# sensor1.net
KiCad netlist of a schematic drawn in EAGLE
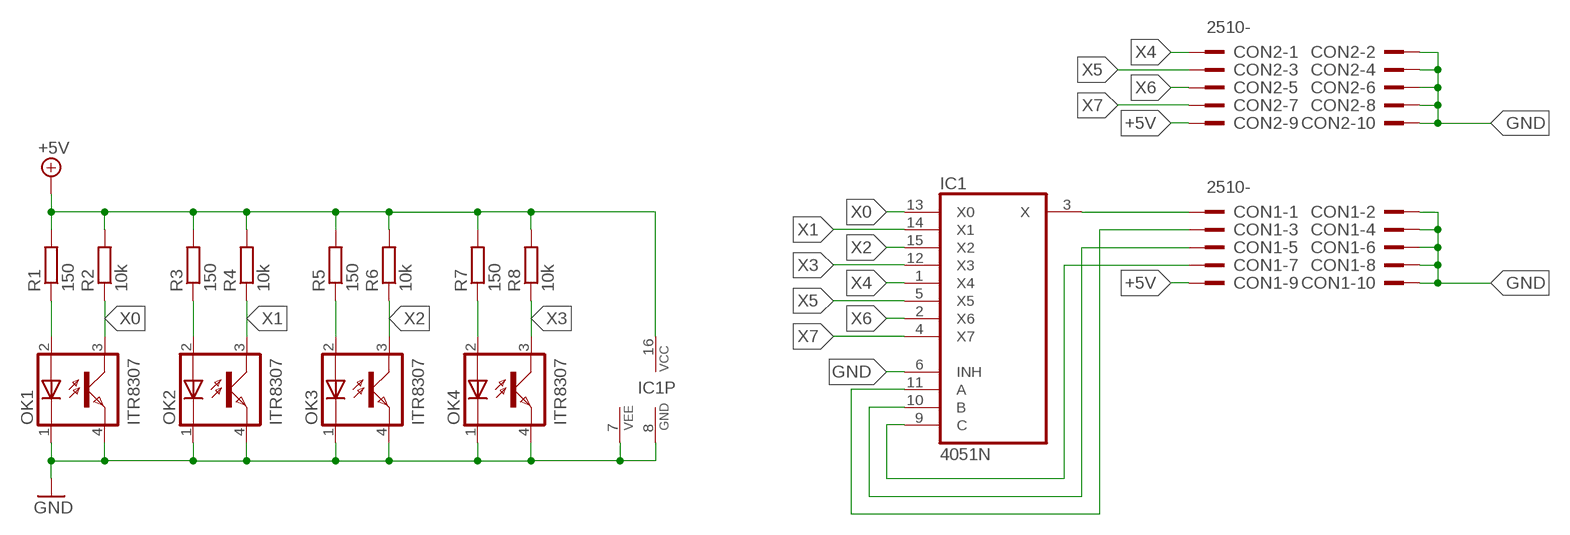
[diagram p0: schematic, sheet 1]

(export (version "E")
  (design (tool "Eeschema 10.0.6"))
  (components
    (comp (ref "CON1")
      (value "2510-")
      (footprint "eagle-import:PAK100_2500-10")
      (fields (field (name "MF") "3M") (field (name "MPN") "2510-6002UB"))
      (libsource (lib "eagle-import") (part "2510-"))
    )
    (comp (ref "CON2")
      (value "2510-")
      (footprint "eagle-import:PAK100_2500-10")
      (fields (field (name "MF") "3M") (field (name "MPN") "2510-6002UB"))
      (libsource (lib "eagle-import") (part "2510-"))
    )
    (comp (ref "IC1")
      (value "4051N")
      (footprint "eagle-import:DIL16")
      (libsource (lib "eagle-import") (part "4051N"))
    )
    (comp (ref "OK1")
      (value "ITR8307")
      (footprint "eagle-import:F43")
      (libsource (lib "eagle-import") (part "ITR8307"))
    )
    (comp (ref "OK2")
      (value "ITR8307")
      (footprint "eagle-import:F43")
      (libsource (lib "eagle-import") (part "ITR8307"))
    )
    (comp (ref "OK3")
      (value "ITR8307")
      (footprint "eagle-import:F43")
      (libsource (lib "eagle-import") (part "ITR8307"))
    )
    (comp (ref "OK4")
      (value "ITR8307")
      (footprint "eagle-import:F43")
      (libsource (lib "eagle-import") (part "ITR8307"))
    )
    (comp (ref "R1")
      (value "150")
      (footprint "eagle-import:0204_7")
      (libsource (lib "eagle-import") (part "R-EU_0204/7"))
    )
    (comp (ref "R2")
      (value "10k")
      (footprint "eagle-import:0204_7")
      (libsource (lib "eagle-import") (part "R-EU_0204/7"))
    )
    (comp (ref "R3")
      (value "150")
      (footprint "eagle-import:0204_7")
      (libsource (lib "eagle-import") (part "R-EU_0204/7"))
    )
    (comp (ref "R4")
      (value "10k")
      (footprint "eagle-import:0204_7")
      (libsource (lib "eagle-import") (part "R-EU_0204/7"))
    )
    (comp (ref "R5")
      (value "150")
      (footprint "eagle-import:0204_7")
      (libsource (lib "eagle-import") (part "R-EU_0204/7"))
    )
    (comp (ref "R6")
      (value "10k")
      (footprint "eagle-import:0204_7")
      (libsource (lib "eagle-import") (part "R-EU_0204/7"))
    )
    (comp (ref "R7")
      (value "150")
      (footprint "eagle-import:0204_7")
      (libsource (lib "eagle-import") (part "R-EU_0204/7"))
    )
    (comp (ref "R8")
      (value "10k")
      (footprint "eagle-import:0204_7")
      (libsource (lib "eagle-import") (part "R-EU_0204/7"))
    )
  )
  (nets
    (net (code "1") (name "+5V") (class "Default")
      (node (ref "CON1") (pin "9") (pinfunction "KL_9") (pintype "passive"))
      (node (ref "CON2") (pin "9") (pinfunction "KL_9") (pintype "passive"))
      (node (ref "IC1") (pin "16") (pinfunction "VCC_16") (pintype "power_in"))
      (node (ref "R1") (pin "2") (pinfunction "2_2") (pintype "passive"))
      (node (ref "R2") (pin "2") (pinfunction "2_2") (pintype "passive"))
      (node (ref "R3") (pin "2") (pinfunction "2_2") (pintype "passive"))
      (node (ref "R4") (pin "2") (pinfunction "2_2") (pintype "passive"))
      (node (ref "R5") (pin "2") (pinfunction "2_2") (pintype "passive"))
      (node (ref "R6") (pin "2") (pinfunction "2_2") (pintype "passive"))
      (node (ref "R7") (pin "2") (pinfunction "2_2") (pintype "passive"))
      (node (ref "R8") (pin "2") (pinfunction "2_2") (pintype "passive"))
    )
    (net (code "2") (name "GND") (class "Default")
      (node (ref "CON1") (pin "10") (pinfunction "KL_10") (pintype "passive"))
      (node (ref "CON1") (pin "2") (pinfunction "KL_2") (pintype "passive"))
      (node (ref "CON1") (pin "4") (pinfunction "KL_4") (pintype "passive"))
      (node (ref "CON1") (pin "6") (pinfunction "KL_6") (pintype "passive"))
      (node (ref "CON1") (pin "8") (pinfunction "KL_8") (pintype "passive"))
      (node (ref "CON2") (pin "10") (pinfunction "KL_10") (pintype "passive"))
      (node (ref "CON2") (pin "2") (pinfunction "KL_2") (pintype "passive"))
      (node (ref "CON2") (pin "4") (pinfunction "KL_4") (pintype "passive"))
      (node (ref "CON2") (pin "6") (pinfunction "KL_6") (pintype "passive"))
      (node (ref "CON2") (pin "8") (pinfunction "KL_8") (pintype "passive"))
      (node (ref "IC1") (pin "6") (pinfunction "INH_6") (pintype "input"))
      (node (ref "IC1") (pin "7") (pinfunction "VEE_7") (pintype "power_in"))
      (node (ref "IC1") (pin "8") (pinfunction "GND_8") (pintype "power_in"))
      (node (ref "OK1") (pin "1") (pinfunction "C_1") (pintype "passive"))
      (node (ref "OK1") (pin "4") (pinfunction "EMIT_4") (pintype "passive"))
      (node (ref "OK2") (pin "1") (pinfunction "C_1") (pintype "passive"))
      (node (ref "OK2") (pin "4") (pinfunction "EMIT_4") (pintype "passive"))
      (node (ref "OK3") (pin "1") (pinfunction "C_1") (pintype "passive"))
      (node (ref "OK3") (pin "4") (pinfunction "EMIT_4") (pintype "passive"))
      (node (ref "OK4") (pin "1") (pinfunction "C_1") (pintype "passive"))
      (node (ref "OK4") (pin "4") (pinfunction "EMIT_4") (pintype "passive"))
    )
    (net (code "3") (name "Net-(CON1A-KL)") (class "Default")
      (node (ref "CON1") (pin "1") (pinfunction "KL_1") (pintype "passive"))
      (node (ref "IC1") (pin "3") (pinfunction "X_3") (pintype "bidirectional"))
    )
    (net (code "4") (name "Net-(CON1D-KL)") (class "Default")
      (node (ref "CON1") (pin "3") (pinfunction "KL_3") (pintype "passive"))
      (node (ref "IC1") (pin "11") (pinfunction "A_11") (pintype "input"))
    )
    (net (code "5") (name "Net-(CON1F-KL)") (class "Default")
      (node (ref "CON1") (pin "5") (pinfunction "KL_5") (pintype "passive"))
      (node (ref "IC1") (pin "10") (pinfunction "B_10") (pintype "input"))
    )
    (net (code "6") (name "Net-(CON1H-KL)") (class "Default")
      (node (ref "CON1") (pin "7") (pinfunction "KL_7") (pintype "passive"))
      (node (ref "IC1") (pin "9") (pinfunction "C_9") (pintype "input"))
    )
    (net (code "7") (name "Net-(OK1-A)") (class "Default")
      (node (ref "OK1") (pin "2") (pinfunction "A_2") (pintype "passive"))
      (node (ref "R1") (pin "1") (pinfunction "1_1") (pintype "passive"))
    )
    (net (code "8") (name "Net-(OK2-A)") (class "Default")
      (node (ref "OK2") (pin "2") (pinfunction "A_2") (pintype "passive"))
      (node (ref "R3") (pin "1") (pinfunction "1_1") (pintype "passive"))
    )
    (net (code "9") (name "Net-(OK3-A)") (class "Default")
      (node (ref "OK3") (pin "2") (pinfunction "A_2") (pintype "passive"))
      (node (ref "R5") (pin "1") (pinfunction "1_1") (pintype "passive"))
    )
    (net (code "10") (name "Net-(OK4-A)") (class "Default")
      (node (ref "OK4") (pin "2") (pinfunction "A_2") (pintype "passive"))
      (node (ref "R7") (pin "1") (pinfunction "1_1") (pintype "passive"))
    )
    (net (code "11") (name "X0") (class "Default")
      (node (ref "IC1") (pin "13") (pinfunction "X0_13") (pintype "bidirectional"))
      (node (ref "OK1") (pin "3") (pinfunction "COL_3") (pintype "passive"))
      (node (ref "R2") (pin "1") (pinfunction "1_1") (pintype "passive"))
    )
    (net (code "12") (name "X1") (class "Default")
      (node (ref "IC1") (pin "14") (pinfunction "X1_14") (pintype "bidirectional"))
      (node (ref "OK2") (pin "3") (pinfunction "COL_3") (pintype "passive"))
      (node (ref "R4") (pin "1") (pinfunction "1_1") (pintype "passive"))
    )
    (net (code "13") (name "X2") (class "Default")
      (node (ref "IC1") (pin "15") (pinfunction "X2_15") (pintype "bidirectional"))
      (node (ref "OK3") (pin "3") (pinfunction "COL_3") (pintype "passive"))
      (node (ref "R6") (pin "1") (pinfunction "1_1") (pintype "passive"))
    )
    (net (code "14") (name "X3") (class "Default")
      (node (ref "IC1") (pin "12") (pinfunction "X3_12") (pintype "bidirectional"))
      (node (ref "OK4") (pin "3") (pinfunction "COL_3") (pintype "passive"))
      (node (ref "R8") (pin "1") (pinfunction "1_1") (pintype "passive"))
    )
    (net (code "15") (name "X4") (class "Default")
      (node (ref "CON2") (pin "1") (pinfunction "KL_1") (pintype "passive"))
      (node (ref "IC1") (pin "1") (pinfunction "X4_1") (pintype "bidirectional"))
    )
    (net (code "16") (name "X5") (class "Default")
      (node (ref "CON2") (pin "3") (pinfunction "KL_3") (pintype "passive"))
      (node (ref "IC1") (pin "5") (pinfunction "X5_5") (pintype "bidirectional"))
    )
    (net (code "17") (name "X6") (class "Default")
      (node (ref "CON2") (pin "5") (pinfunction "KL_5") (pintype "passive"))
      (node (ref "IC1") (pin "2") (pinfunction "X6_2") (pintype "bidirectional"))
    )
    (net (code "18") (name "X7") (class "Default")
      (node (ref "CON2") (pin "7") (pinfunction "KL_7") (pintype "passive"))
      (node (ref "IC1") (pin "4") (pinfunction "X7_4") (pintype "bidirectional"))
    )
  )
)
